# PROC054D_Temp_Sensor.net
KiCad netlist of a schematic drawn in Altium Designer
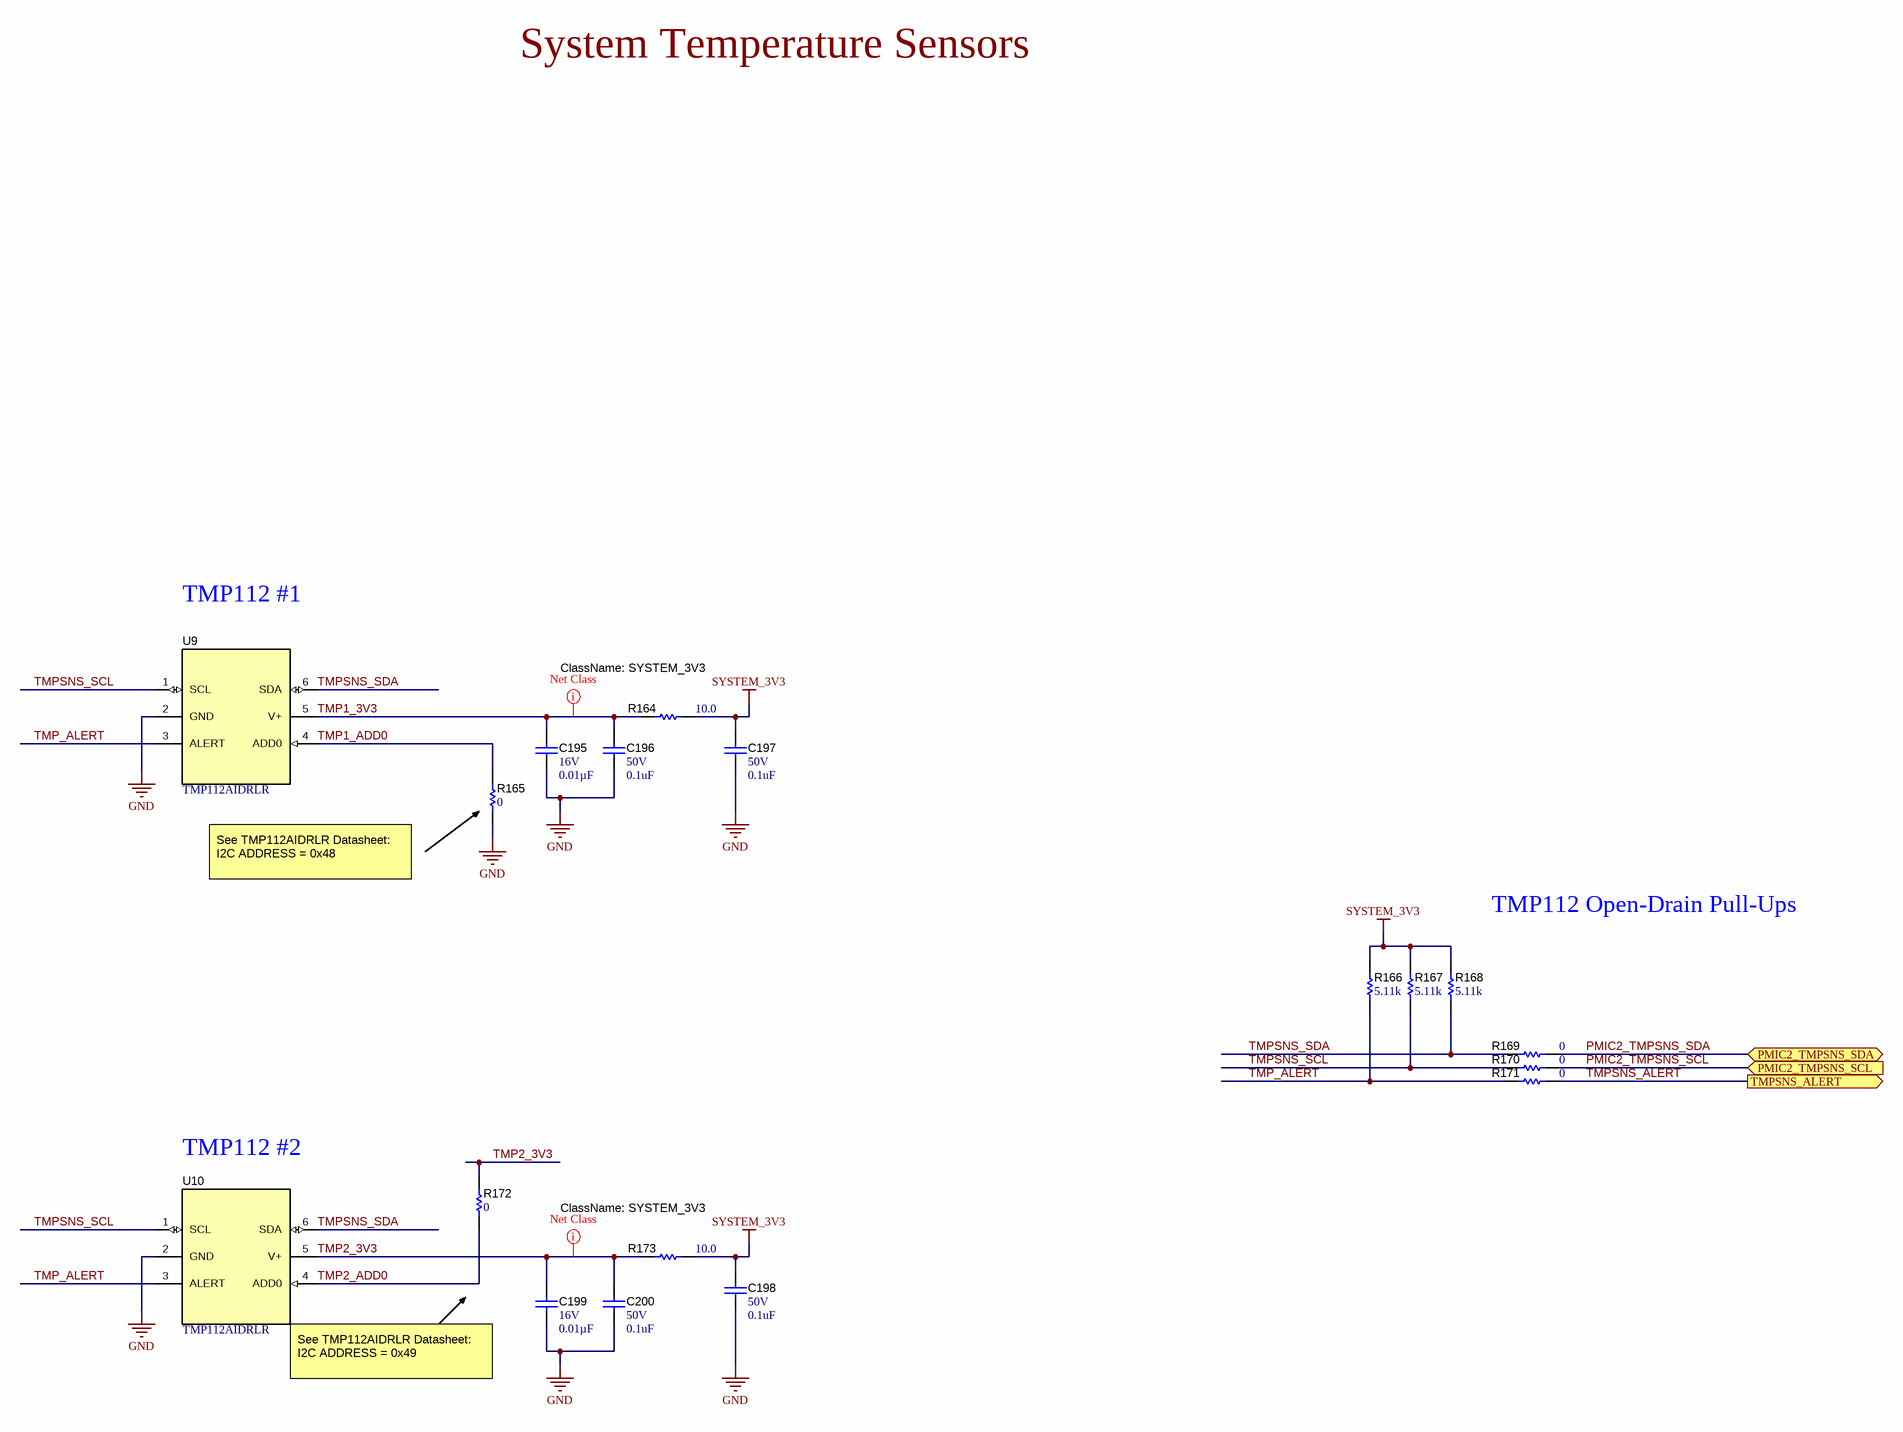
[diagram p0: PROC054D_Temp_Sensor.SchDoc]

(export (version "E")
  (design (tool "Eeschema 10.0.6"))
  (components
    (comp (ref "C195")
      (value "C0402C103K4RACTU")
      (footprint "0402")
      (description "CAP, CERM, 0.01 µF, 16 V,+/- 10%, X7R, 0402")
      (fields
        (field (name "MANUFACTURER") "Kemet")
        (field (name "VDC_V") "16V")
        (field (name "VALUEDISPLAYED") "0.01µF")
      )
      (libsource (lib "Altium Vault - TI") (part "Capacitor"))
    )
    (comp (ref "C196")
      (value "CGA2B3X7R1H104K050BB")
      (footprint "0402")
      (description "CAP, CERM, 0.1 uF, 50 V, +/- 10%, X7R, AEC-Q200 Grade 1, 0402")
      (fields
        (field (name "MANUFACTURER") "TDK")
        (field (name "VDC_V") "50V")
        (field (name "VALUEDISPLAYED") "0.1uF")
        (field (name "PUBLISHER") "Texas Instruments")
      )
      (libsource (lib "Altium Vault - TI") (part "Capacitor"))
    )
    (comp (ref "C197")
      (value "CGA2B3X7R1H104K050BB")
      (footprint "0402")
      (description "CAP, CERM, 0.1 uF, 50 V, +/- 10%, X7R, AEC-Q200 Grade 1, 0402")
      (fields
        (field (name "MANUFACTURER") "TDK")
        (field (name "VDC_V") "50V")
        (field (name "VALUEDISPLAYED") "0.1uF")
        (field (name "PUBLISHER") "Texas Instruments")
      )
      (libsource (lib "Altium Vault - TI") (part "Capacitor"))
    )
    (comp (ref "C198")
      (value "CGA2B3X7R1H104K050BB")
      (footprint "0402")
      (description "CAP, CERM, 0.1 uF, 50 V, +/- 10%, X7R, AEC-Q200 Grade 1, 0402")
      (fields
        (field (name "MANUFACTURER") "TDK")
        (field (name "VDC_V") "50V")
        (field (name "VALUEDISPLAYED") "0.1uF")
        (field (name "PUBLISHER") "Texas Instruments")
      )
      (libsource (lib "Altium Vault - TI") (part "Capacitor"))
    )
    (comp (ref "C199")
      (value "C0402C103K4RACTU")
      (footprint "0402")
      (description "CAP, CERM, 0.01 µF, 16 V,+/- 10%, X7R, 0402")
      (fields
        (field (name "MANUFACTURER") "Kemet")
        (field (name "VDC_V") "16V")
        (field (name "VALUEDISPLAYED") "0.01µF")
      )
      (libsource (lib "Altium Vault - TI") (part "Capacitor"))
    )
    (comp (ref "C200")
      (value "CGA2B3X7R1H104K050BB")
      (footprint "0402")
      (description "CAP, CERM, 0.1 uF, 50 V, +/- 10%, X7R, AEC-Q200 Grade 1, 0402")
      (fields
        (field (name "MANUFACTURER") "TDK")
        (field (name "VDC_V") "50V")
        (field (name "VALUEDISPLAYED") "0.1uF")
        (field (name "PUBLISHER") "Texas Instruments")
      )
      (libsource (lib "Altium Vault - TI") (part "Capacitor"))
    )
    (comp (ref "R164")
      (value "CRCW040210R0FKED")
      (footprint "0402")
      (description "RES, 10.0, 1%, 0.063 W, AEC-Q200 Grade 0, 0402")
      (fields (field (name "MANUFACTURER") "Vishay-Dale") (field (name "VALUEDISPLAYED") "10.0"))
      (libsource (lib "Altium Vault - TI") (part "Resistor"))
    )
    (comp (ref "R165")
      (value "ERJ-2GE0R00X")
      (footprint "0402")
      (description "RES, 0, 5%, 0.1 W, AEC-Q200 Grade 0, 0402")
      (fields (field (name "MANUFACTURER") "Panasonic") (field (name "VALUEDISPLAYED") "0"))
      (libsource (lib "Altium Vault - TI") (part "CMP-0026992-3"))
    )
    (comp (ref "R166")
      (value "CRCW04025K11FKED")
      (footprint "0402")
      (description "RES, 5.11 k, 1%, 0.063 W, AEC-Q200 Grade 0, 0402")
      (fields (field (name "MANUFACTURER") "Vishay-Dale") (field (name "VALUEDISPLAYED") "5.11k"))
      (libsource (lib "Altium Vault - TI") (part "CMP-0026463-2"))
    )
    (comp (ref "R167")
      (value "CRCW04025K11FKED")
      (footprint "0402")
      (description "RES, 5.11 k, 1%, 0.063 W, AEC-Q200 Grade 0, 0402")
      (fields (field (name "MANUFACTURER") "Vishay-Dale") (field (name "VALUEDISPLAYED") "5.11k"))
      (libsource (lib "Altium Vault - TI") (part "CMP-0026463-2"))
    )
    (comp (ref "R168")
      (value "CRCW04025K11FKED")
      (footprint "0402")
      (description "RES, 5.11 k, 1%, 0.063 W, AEC-Q200 Grade 0, 0402")
      (fields (field (name "MANUFACTURER") "Vishay-Dale") (field (name "VALUEDISPLAYED") "5.11k"))
      (libsource (lib "Altium Vault - TI") (part "CMP-0026463-2"))
    )
    (comp (ref "R169")
      (value "ERJ-2GE0R00X")
      (footprint "0402")
      (description "RES, 0, 5%, 0.1 W, AEC-Q200 Grade 0, 0402")
      (fields (field (name "MANUFACTURER") "Panasonic") (field (name "VALUEDISPLAYED") "0"))
      (libsource (lib "Altium Vault - TI") (part "Resistor"))
    )
    (comp (ref "R170")
      (value "ERJ-2GE0R00X")
      (footprint "0402")
      (description "RES, 0, 5%, 0.1 W, AEC-Q200 Grade 0, 0402")
      (fields (field (name "MANUFACTURER") "Panasonic") (field (name "VALUEDISPLAYED") "0"))
      (libsource (lib "Altium Vault - TI") (part "Resistor"))
    )
    (comp (ref "R171")
      (value "ERJ-2GE0R00X")
      (footprint "0402")
      (description "RES, 0, 5%, 0.1 W, AEC-Q200 Grade 0, 0402")
      (fields (field (name "MANUFACTURER") "Panasonic") (field (name "VALUEDISPLAYED") "0"))
      (libsource (lib "Altium Vault - TI") (part "Resistor"))
    )
    (comp (ref "R172")
      (value "ERJ-2GE0R00X")
      (footprint "0402")
      (description "RES, 0, 5%, 0.1 W, AEC-Q200 Grade 0, 0402")
      (fields (field (name "MANUFACTURER") "Panasonic") (field (name "VALUEDISPLAYED") "0"))
      (libsource (lib "Altium Vault - TI") (part "CMP-0026992-3"))
    )
    (comp (ref "R173")
      (value "CRCW040210R0FKED")
      (footprint "0402")
      (description "RES, 10.0, 1%, 0.063 W, AEC-Q200 Grade 0, 0402")
      (fields (field (name "MANUFACTURER") "Vishay-Dale") (field (name "VALUEDISPLAYED") "10.0"))
      (libsource (lib "Altium Vault - TI") (part "Resistor"))
    )
    (comp (ref "U9")
      (value "TMP112AIDRLR")
      (footprint "DRL0006A")
      (fields
        (field (name "ALTERNATE PARTNUMBER") "TMP112AIDRLT")
        (field (name "MANUFACTURER") "Texas Instruments")
        (field (name "PARTNUMBER") "TMP112AIDRLR")
        (field (name "PUBLISHER") "Texas Instruments")
      )
      (libsource (lib "Altium Vault - TI") (part "CMP-0067397-2"))
    )
    (comp (ref "U10")
      (value "TMP112AIDRLR")
      (footprint "DRL0006A")
      (fields
        (field (name "ALTERNATE PARTNUMBER") "TMP112AIDRLT")
        (field (name "MANUFACTURER") "Texas Instruments")
        (field (name "PARTNUMBER") "TMP112AIDRLR")
        (field (name "PUBLISHER") "Texas Instruments")
      )
      (libsource (lib "Altium Vault - TI") (part "CMP-0067397-2"))
    )
  )
  (nets
    (net (code "1") (name "/PMIC2_TMPSNS_SCL") (class "Default")
      (node (ref "R170") (pin "2") (pinfunction "2_2") (pintype "passive"))
    )
    (net (code "2") (name "/PMIC2_TMPSNS_SDA") (class "Default")
      (node (ref "R169") (pin "2") (pinfunction "2_2") (pintype "passive"))
    )
    (net (code "3") (name "/TMP1_3V3") (class "Default")
      (node (ref "C195") (pin "1") (pinfunction "1_1") (pintype "passive"))
      (node (ref "C196") (pin "1") (pinfunction "1_1") (pintype "passive"))
      (node (ref "R164") (pin "2") (pinfunction "2_2") (pintype "passive"))
      (node (ref "U9") (pin "5") (pinfunction "V+_5") (pintype "power_in"))
    )
    (net (code "4") (name "/TMP1_ADD0") (class "Default")
      (node (ref "R165") (pin "2") (pinfunction "2_2") (pintype "passive"))
      (node (ref "U9") (pin "4") (pinfunction "ADD0_4") (pintype "input"))
    )
    (net (code "5") (name "/TMP2_3V3") (class "Default")
      (node (ref "C199") (pin "1") (pinfunction "1_1") (pintype "passive"))
      (node (ref "C200") (pin "1") (pinfunction "1_1") (pintype "passive"))
      (node (ref "R172") (pin "2") (pinfunction "2_2") (pintype "passive"))
      (node (ref "R173") (pin "2") (pinfunction "2_2") (pintype "passive"))
      (node (ref "U10") (pin "5") (pinfunction "V+_5") (pintype "power_in"))
    )
    (net (code "6") (name "/TMP2_ADD0") (class "Default")
      (node (ref "R172") (pin "1") (pinfunction "1_1") (pintype "passive"))
      (node (ref "U10") (pin "4") (pinfunction "ADD0_4") (pintype "input"))
    )
    (net (code "7") (name "/TMPSNS_ALERT") (class "Default")
      (node (ref "R171") (pin "2") (pinfunction "2_2") (pintype "passive"))
    )
    (net (code "8") (name "/TMPSNS_SCL") (class "Default")
      (node (ref "R167") (pin "1") (pinfunction "1_1") (pintype "passive"))
      (node (ref "R170") (pin "1") (pinfunction "1_1") (pintype "passive"))
      (node (ref "U10") (pin "1") (pinfunction "SCL_1") (pintype "bidirectional"))
      (node (ref "U9") (pin "1") (pinfunction "SCL_1") (pintype "bidirectional"))
    )
    (net (code "9") (name "/TMPSNS_SDA") (class "Default")
      (node (ref "R168") (pin "1") (pinfunction "1_1") (pintype "passive"))
      (node (ref "R169") (pin "1") (pinfunction "1_1") (pintype "passive"))
      (node (ref "U10") (pin "6") (pinfunction "SDA_6") (pintype "bidirectional"))
      (node (ref "U9") (pin "6") (pinfunction "SDA_6") (pintype "bidirectional"))
    )
    (net (code "10") (name "/TMP_ALERT") (class "Default")
      (node (ref "R166") (pin "1") (pinfunction "1_1") (pintype "passive"))
      (node (ref "R171") (pin "1") (pinfunction "1_1") (pintype "passive"))
      (node (ref "U10") (pin "3") (pinfunction "ALERT_3") (pintype "open_collector"))
      (node (ref "U9") (pin "3") (pinfunction "ALERT_3") (pintype "open_collector"))
    )
    (net (code "11") (name "GND") (class "Default")
      (node (ref "C195") (pin "2") (pinfunction "2_2") (pintype "passive"))
      (node (ref "C196") (pin "2") (pinfunction "2_2") (pintype "passive"))
      (node (ref "C197") (pin "2") (pinfunction "2_2") (pintype "passive"))
      (node (ref "C198") (pin "2") (pinfunction "2_2") (pintype "passive"))
      (node (ref "C199") (pin "2") (pinfunction "2_2") (pintype "passive"))
      (node (ref "C200") (pin "2") (pinfunction "2_2") (pintype "passive"))
      (node (ref "R165") (pin "1") (pinfunction "1_1") (pintype "passive"))
      (node (ref "U10") (pin "2") (pinfunction "GND_2") (pintype "power_in"))
      (node (ref "U9") (pin "2") (pinfunction "GND_2") (pintype "power_in"))
    )
    (net (code "12") (name "SYSTEM_3V3") (class "Default")
      (node (ref "C197") (pin "1") (pinfunction "1_1") (pintype "passive"))
      (node (ref "C198") (pin "1") (pinfunction "1_1") (pintype "passive"))
      (node (ref "R164") (pin "1") (pinfunction "1_1") (pintype "passive"))
      (node (ref "R166") (pin "2") (pinfunction "2_2") (pintype "passive"))
      (node (ref "R167") (pin "2") (pinfunction "2_2") (pintype "passive"))
      (node (ref "R168") (pin "2") (pinfunction "2_2") (pintype "passive"))
      (node (ref "R173") (pin "1") (pinfunction "1_1") (pintype "passive"))
    )
  )
)
